# LNB.net
KiCad netlist of a schematic drawn in EAGLE
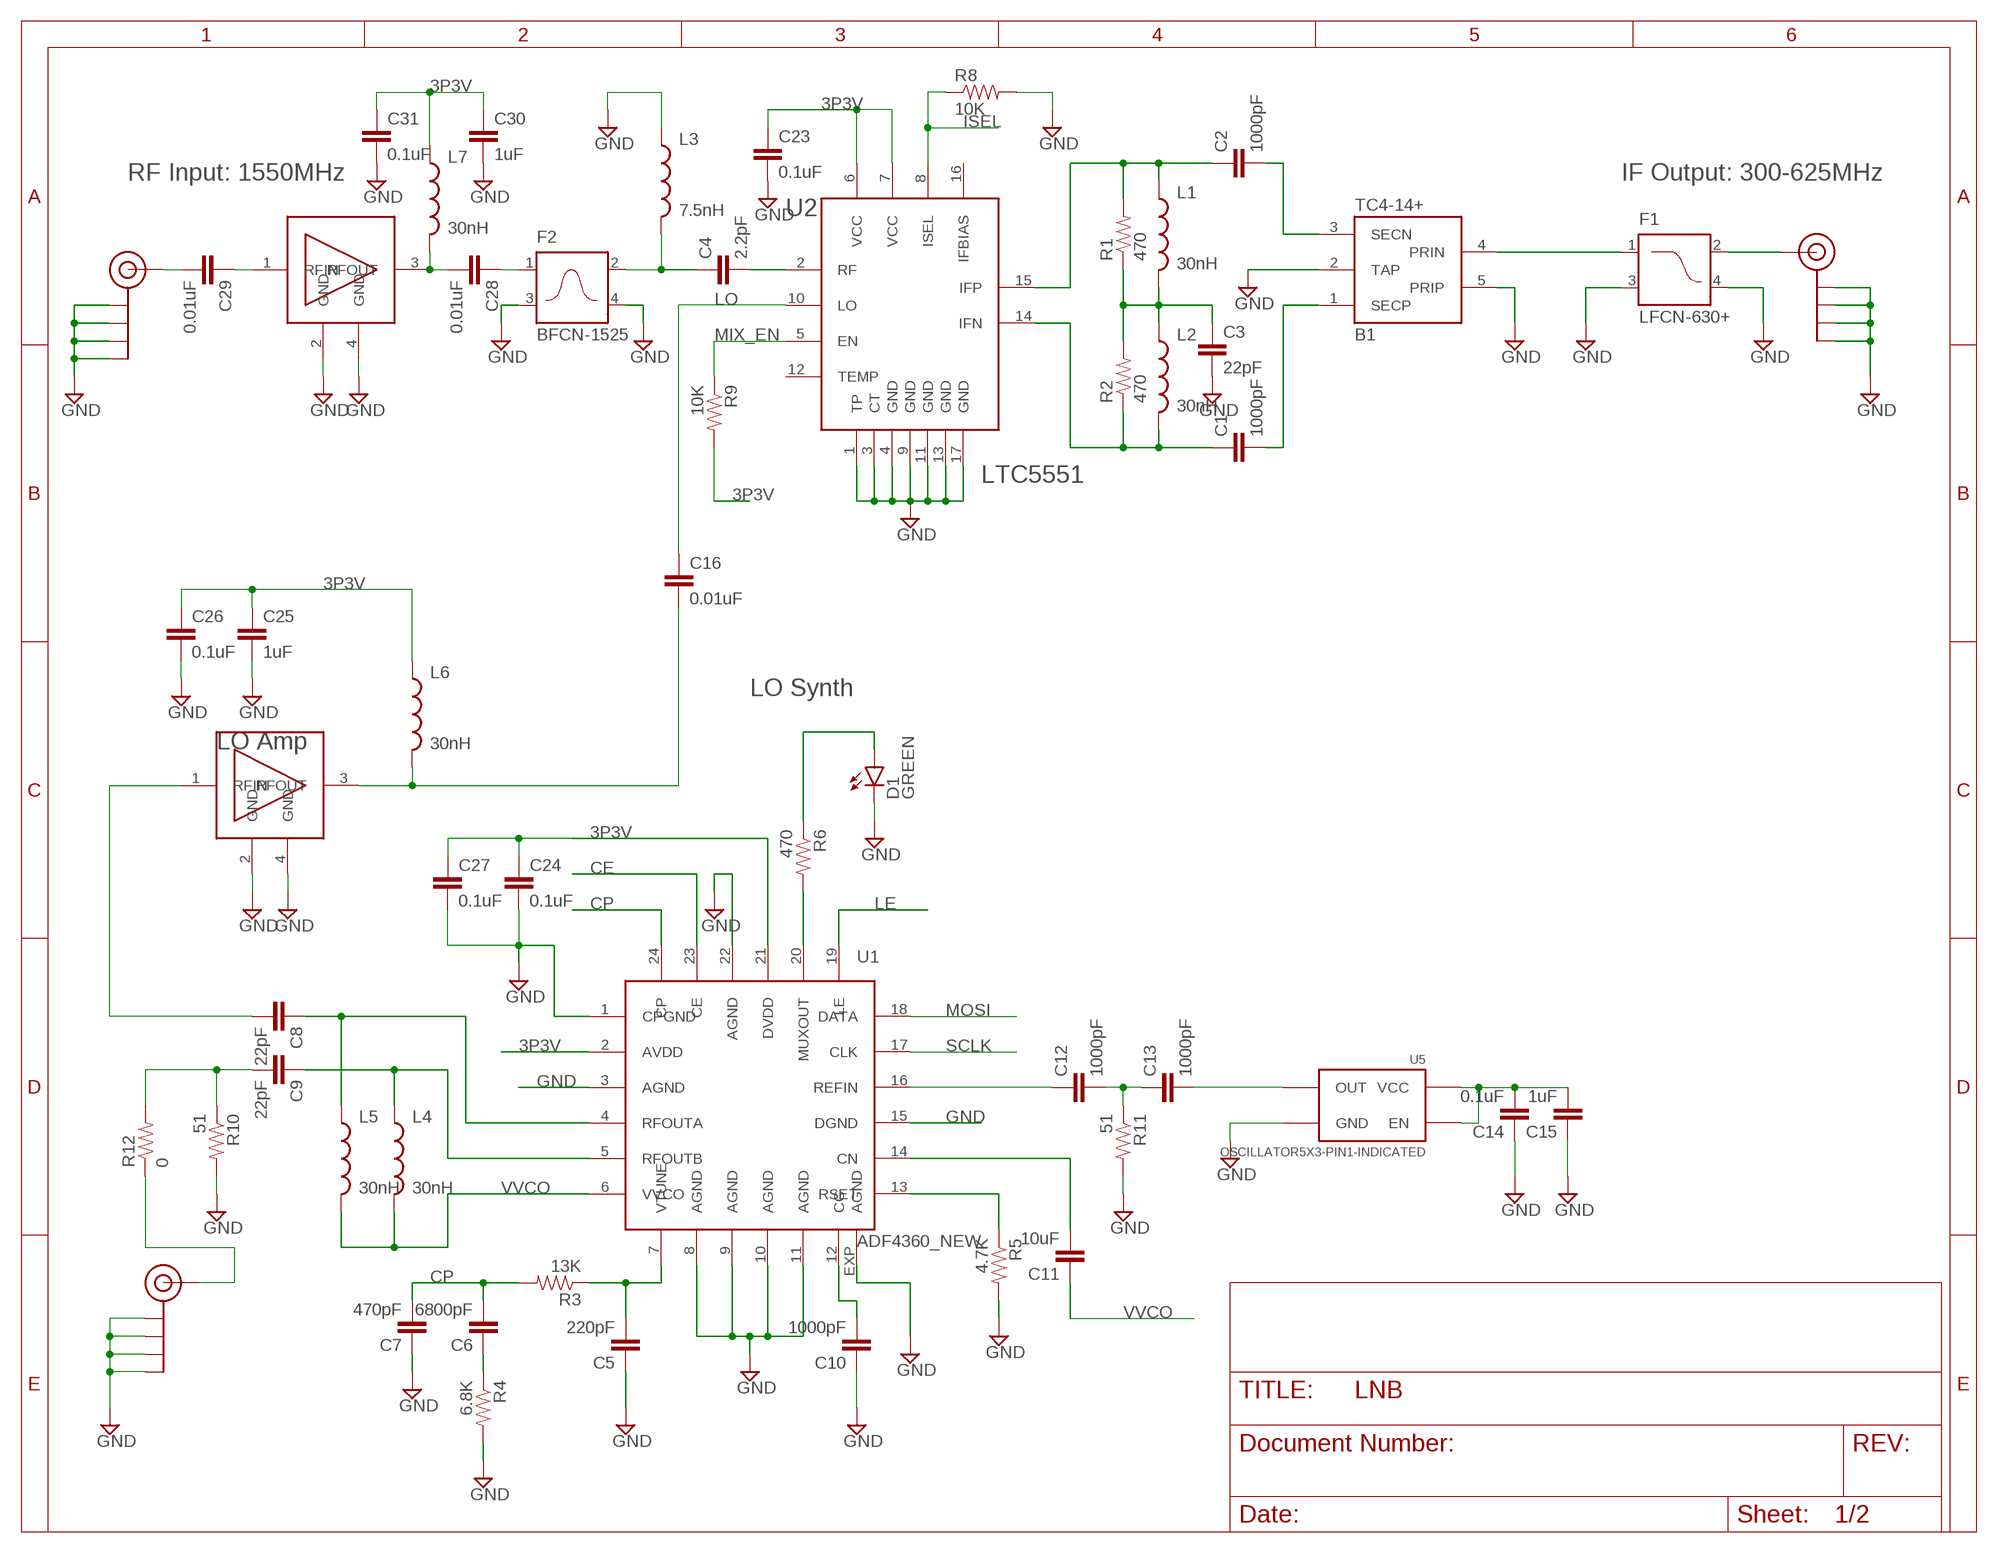
[diagram p0: schematic, sheet 1]
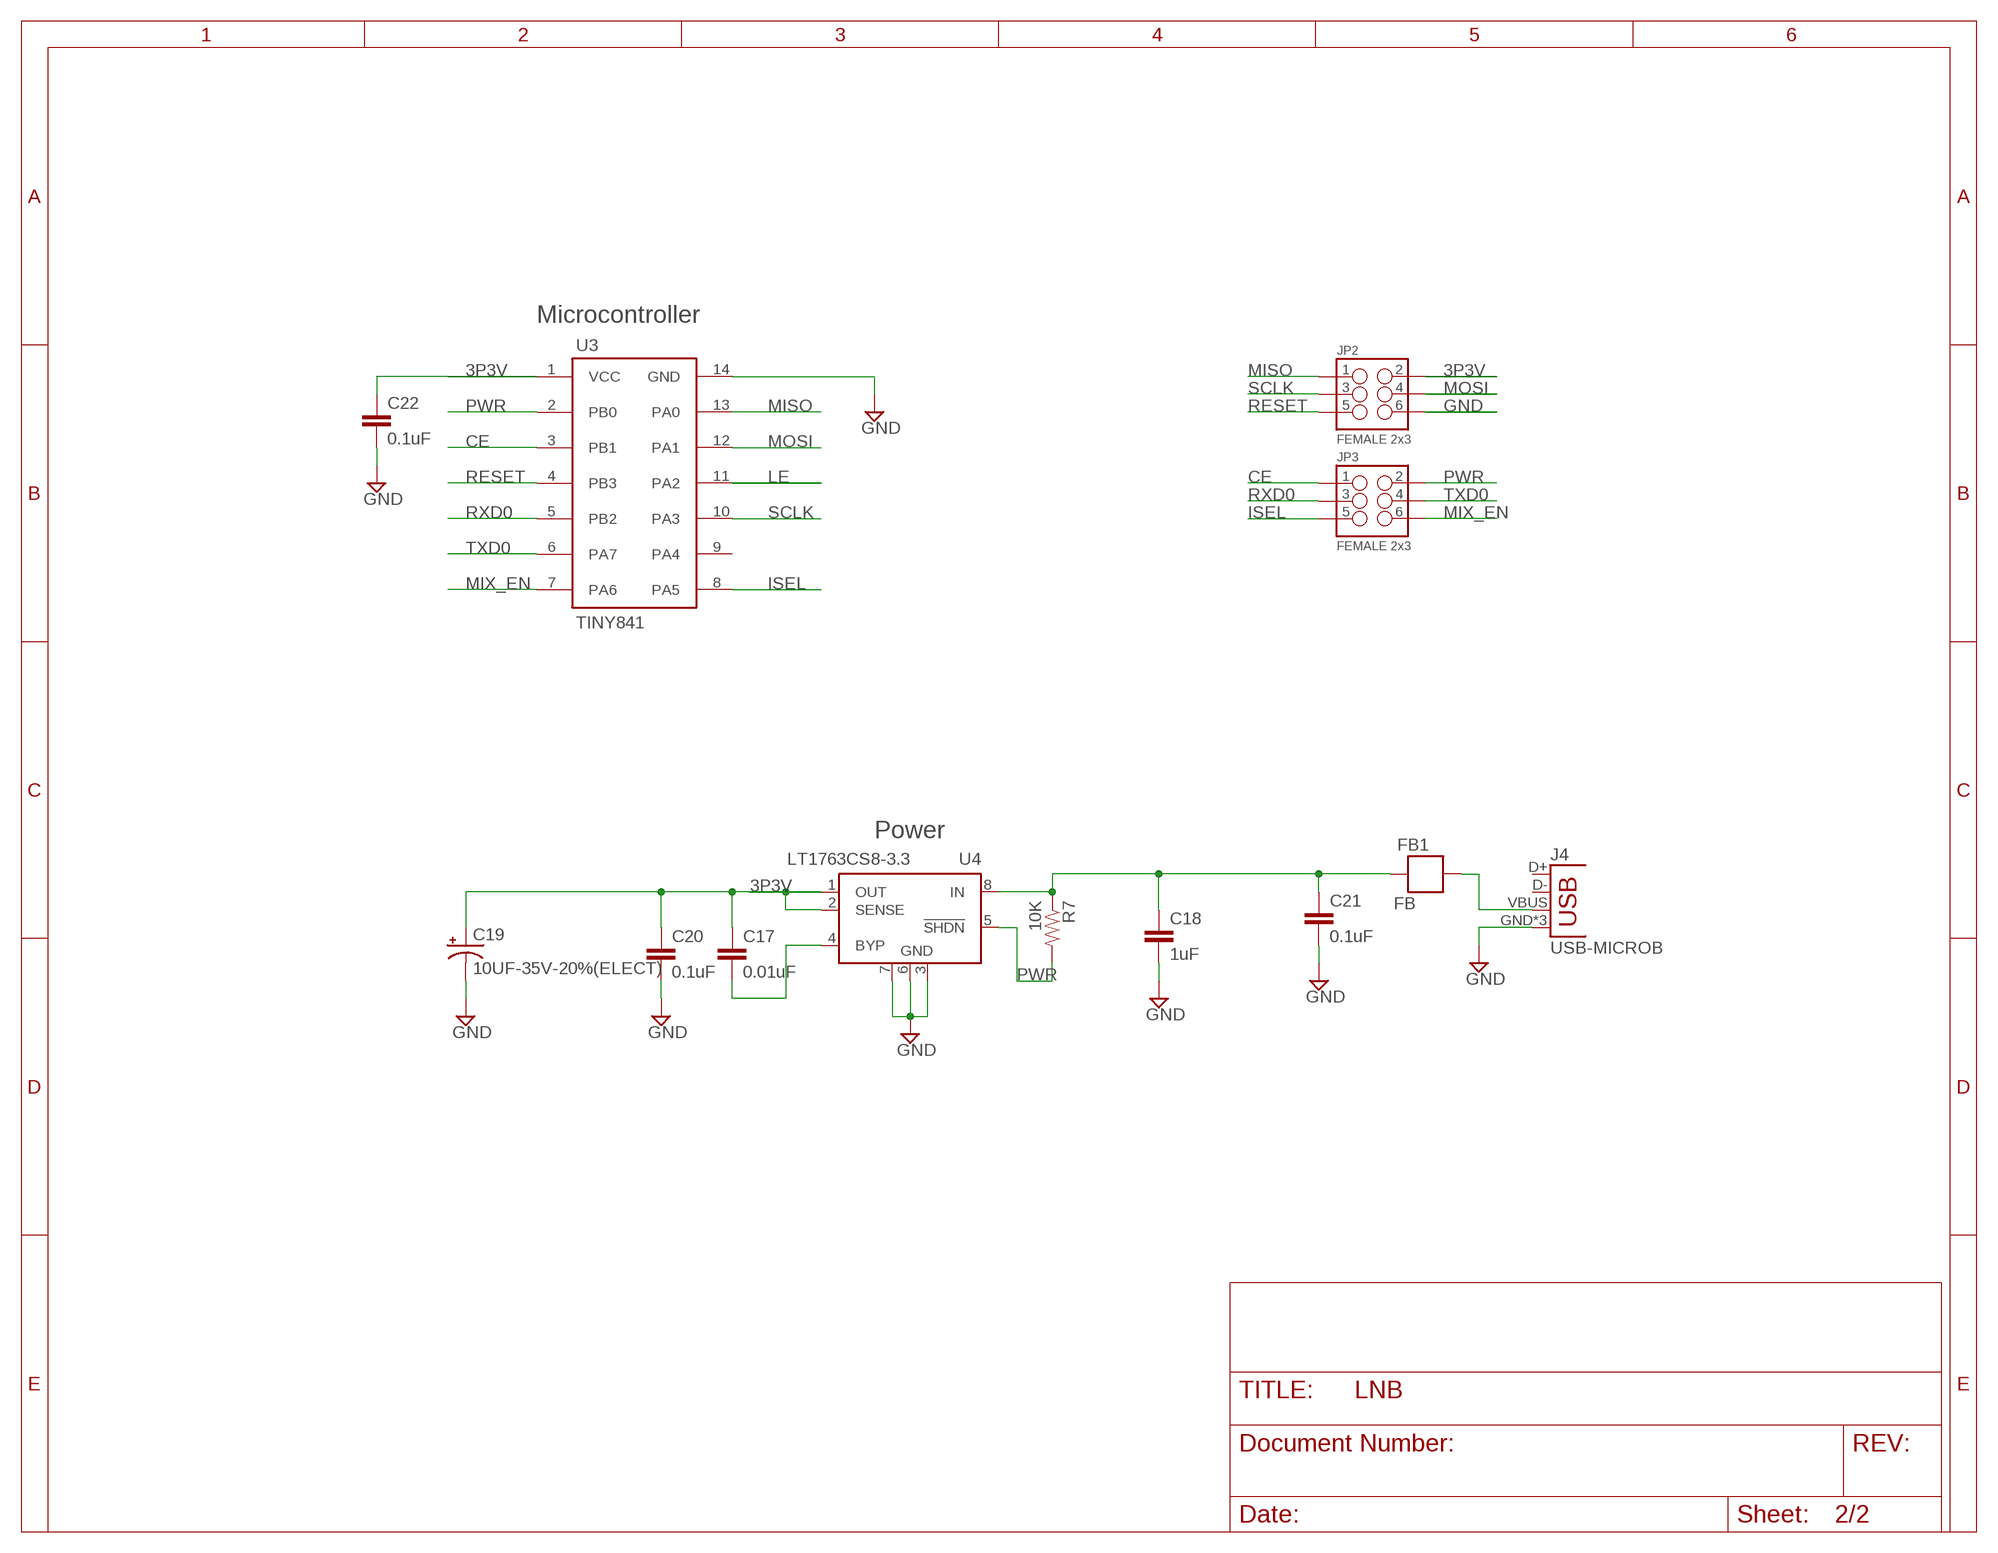
[diagram p1: schematic, sheet 2]

(export (version "E")
  (design (tool "Eeschema 10.0.6"))
  (components
    (comp (ref "B1")
      (value "TC4-14+")
      (footprint "eagle-import:AT224-1")
      (libsource (lib "eagle-import") (part "TC4-14+"))
    )
    (comp (ref "C1")
      (value "1000pF")
      (footprint "eagle-import:0603-CAP")
      (libsource (lib "eagle-import") (part "CAP0603-CAP"))
    )
    (comp (ref "C2")
      (value "1000pF")
      (footprint "eagle-import:0603-CAP")
      (libsource (lib "eagle-import") (part "CAP0603-CAP"))
    )
    (comp (ref "C3")
      (value "22pF")
      (footprint "eagle-import:0603-CAP")
      (libsource (lib "eagle-import") (part "CAP0603-CAP"))
    )
    (comp (ref "C4")
      (value "2.2pF")
      (footprint "eagle-import:0603-CAP")
      (libsource (lib "eagle-import") (part "CAP0603-CAP"))
    )
    (comp (ref "C5")
      (value "220pF")
      (footprint "eagle-import:0603-CAP")
      (libsource (lib "eagle-import") (part "CAP0603-CAP"))
    )
    (comp (ref "C6")
      (value "6800pF")
      (footprint "eagle-import:0603-CAP")
      (libsource (lib "eagle-import") (part "CAP0603-CAP"))
    )
    (comp (ref "C7")
      (value "470pF")
      (footprint "eagle-import:0603-CAP")
      (libsource (lib "eagle-import") (part "CAP0603-CAP"))
    )
    (comp (ref "C8")
      (value "22pF")
      (footprint "eagle-import:0603-CAP")
      (libsource (lib "eagle-import") (part "CAP0603-CAP"))
    )
    (comp (ref "C9")
      (value "22pF")
      (footprint "eagle-import:0603-CAP")
      (libsource (lib "eagle-import") (part "CAP0603-CAP"))
    )
    (comp (ref "C10")
      (value "1000pF")
      (footprint "eagle-import:0603-CAP")
      (libsource (lib "eagle-import") (part "CAP0603-CAP"))
    )
    (comp (ref "C11")
      (value "10uF")
      (footprint "eagle-import:0603-CAP")
      (libsource (lib "eagle-import") (part "CAP0603-CAP"))
    )
    (comp (ref "C12")
      (value "1000pF")
      (footprint "eagle-import:0603-CAP")
      (libsource (lib "eagle-import") (part "CAP0603-CAP"))
    )
    (comp (ref "C13")
      (value "1000pF")
      (footprint "eagle-import:0603-CAP")
      (libsource (lib "eagle-import") (part "CAP0603-CAP"))
    )
    (comp (ref "C14")
      (value "0.1uF")
      (footprint "eagle-import:0603-CAP")
      (libsource (lib "eagle-import") (part "CAP0603-CAP"))
    )
    (comp (ref "C15")
      (value "1uF")
      (footprint "eagle-import:0603-CAP")
      (libsource (lib "eagle-import") (part "CAP0603-CAP"))
    )
    (comp (ref "C16")
      (value "0.01uF")
      (footprint "eagle-import:0603-CAP")
      (libsource (lib "eagle-import") (part "CAP0603-CAP"))
    )
    (comp (ref "C23")
      (value "0.1uF")
      (footprint "eagle-import:0603-CAP")
      (libsource (lib "eagle-import") (part "CAP0603-CAP"))
    )
    (comp (ref "C24")
      (value "0.1uF")
      (footprint "eagle-import:0603-CAP")
      (libsource (lib "eagle-import") (part "CAP0603-CAP"))
    )
    (comp (ref "C25")
      (value "1uF")
      (footprint "eagle-import:1206")
      (libsource (lib "eagle-import") (part "CAP1206"))
    )
    (comp (ref "C26")
      (value "0.1uF")
      (footprint "eagle-import:0603-CAP")
      (libsource (lib "eagle-import") (part "CAP0603-CAP"))
    )
    (comp (ref "C27")
      (value "0.1uF")
      (footprint "eagle-import:0603-CAP")
      (libsource (lib "eagle-import") (part "CAP0603-CAP"))
    )
    (comp (ref "C28")
      (value "0.01uF")
      (footprint "eagle-import:0603-CAP")
      (libsource (lib "eagle-import") (part "CAP0603-CAP"))
    )
    (comp (ref "C29")
      (value "0.01uF")
      (footprint "eagle-import:0603-CAP")
      (libsource (lib "eagle-import") (part "CAP0603-CAP"))
    )
    (comp (ref "C30")
      (value "1uF")
      (footprint "eagle-import:1206")
      (libsource (lib "eagle-import") (part "CAP1206"))
    )
    (comp (ref "C31")
      (value "0.1uF")
      (footprint "eagle-import:0603-CAP")
      (libsource (lib "eagle-import") (part "CAP0603-CAP"))
    )
    (comp (ref "D1")
      (value "GREEN")
      (footprint "eagle-import:LED-0603")
      (libsource (lib "eagle-import") (part "LED-GREEN0603"))
    )
    (comp (ref "F1")
      (value "LFCN-630+")
      (footprint "eagle-import:FV1206_MC")
      (libsource (lib "eagle-import") (part "LFCN-630+"))
    )
    (comp (ref "F2")
      (value "BFCN-1525")
      (footprint "eagle-import:FV1206_MC")
      (libsource (lib "eagle-import") (part "BFCN-1525"))
    )
    (comp (ref "J$1")
      (value "SMA_EDGE")
      (footprint "eagle-import:SMA-EDGE")
      (libsource (lib "eagle-import") (part "SMA_EDGE"))
    )
    (comp (ref "J2")
      (value "SMA_EDGE")
      (footprint "eagle-import:SMA-EDGE")
      (libsource (lib "eagle-import") (part "SMA_EDGE"))
    )
    (comp (ref "J3")
      (value "SMA_EDGE")
      (footprint "eagle-import:SMA-EDGE")
      (libsource (lib "eagle-import") (part "SMA_EDGE"))
    )
    (comp (ref "L1")
      (value "30nH")
      (footprint "eagle-import:0603")
      (libsource (lib "eagle-import") (part "INDUCTOR30OHM,1.8A"))
    )
    (comp (ref "L2")
      (value "30nH")
      (footprint "eagle-import:0603")
      (libsource (lib "eagle-import") (part "INDUCTOR30OHM,1.8A"))
    )
    (comp (ref "L3")
      (value "7.5nH")
      (footprint "eagle-import:0603")
      (libsource (lib "eagle-import") (part "INDUCTOR30OHM,1.8A"))
    )
    (comp (ref "L4")
      (value "30nH")
      (footprint "eagle-import:0603")
      (libsource (lib "eagle-import") (part "INDUCTOR30OHM,1.8A"))
    )
    (comp (ref "L5")
      (value "30nH")
      (footprint "eagle-import:0603")
      (libsource (lib "eagle-import") (part "INDUCTOR30OHM,1.8A"))
    )
    (comp (ref "L6")
      (value "30nH")
      (footprint "eagle-import:0603")
      (libsource (lib "eagle-import") (part "INDUCTOR30OHM,1.8A"))
    )
    (comp (ref "L7")
      (value "30nH")
      (footprint "eagle-import:0603")
      (libsource (lib "eagle-import") (part "INDUCTOR30OHM,1.8A"))
    )
    (comp (ref "R1")
      (value "470")
      (footprint "eagle-import:0603-RES")
      (libsource (lib "eagle-import") (part "RESISTOR0603-RES"))
    )
    (comp (ref "R2")
      (value "470")
      (footprint "eagle-import:0603-RES")
      (libsource (lib "eagle-import") (part "RESISTOR0603-RES"))
    )
    (comp (ref "R3")
      (value "13K")
      (footprint "eagle-import:0603-RES")
      (libsource (lib "eagle-import") (part "RESISTOR0603-RES"))
    )
    (comp (ref "R4")
      (value "6.8K")
      (footprint "eagle-import:0603-RES")
      (libsource (lib "eagle-import") (part "RESISTOR0603-RES"))
    )
    (comp (ref "R5")
      (value "4.7K")
      (footprint "eagle-import:0603-RES")
      (libsource (lib "eagle-import") (part "RESISTOR0603-RES"))
    )
    (comp (ref "R6")
      (value "470")
      (footprint "eagle-import:0603-RES")
      (libsource (lib "eagle-import") (part "RESISTOR0603-RES"))
    )
    (comp (ref "R8")
      (value "10K")
      (footprint "eagle-import:0603-RES")
      (libsource (lib "eagle-import") (part "RESISTOR0603-RES"))
    )
    (comp (ref "R9")
      (value "10K")
      (footprint "eagle-import:0603-RES")
      (libsource (lib "eagle-import") (part "RESISTOR0603-RES"))
    )
    (comp (ref "R10")
      (value "51")
      (footprint "eagle-import:0603-RES")
      (libsource (lib "eagle-import") (part "RESISTOR0603-RES"))
    )
    (comp (ref "R11")
      (value "51")
      (footprint "eagle-import:0603-RES")
      (libsource (lib "eagle-import") (part "RESISTOR0603-RES"))
    )
    (comp (ref "R12")
      (value "0")
      (footprint "eagle-import:0603-RES")
      (libsource (lib "eagle-import") (part "RESISTOR0603-RES"))
    )
    (comp (ref "U1")
      (value "ADF4360_NEW")
      (footprint "eagle-import:LFCSP24")
      (libsource (lib "eagle-import") (part "ADF4360_NEW"))
    )
    (comp (ref "U2")
      (value "LTC5551")
      (footprint "eagle-import:QFN16-4X4")
      (libsource (lib "eagle-import") (part "LTC5551"))
    )
    (comp (ref "U5")
      (value "OSCILLATOR5X3-PIN1-INDICATED")
      (footprint "eagle-import:CRYSTAL-OSC-SMD-5X3")
      (libsource (lib "eagle-import") (part "OSCILLATOR5X3-PIN1-INDICATED"))
    )
    (comp (ref "U6")
      (value "PGA-105+")
      (footprint "eagle-import:SOT-89")
      (libsource (lib "eagle-import") (part "PGA-105+"))
    )
    (comp (ref "U7")
      (value "PGA-105+")
      (footprint "eagle-import:SOT-89")
      (libsource (lib "eagle-import") (part "PGA-105+"))
    )
    (comp (ref "C17")
      (value "0.01uF")
      (footprint "eagle-import:0603-CAP")
      (libsource (lib "eagle-import") (part "CAP0603-CAP"))
    )
    (comp (ref "C18")
      (value "1uF")
      (footprint "eagle-import:1206")
      (libsource (lib "eagle-import") (part "CAP1206"))
    )
    (comp (ref "C19")
      (value "10UF-35V-20%(ELECT)")
      (footprint "eagle-import:PANASONIC_C")
      (libsource (lib "eagle-import") (part "10UF-35V-20%(ELECT)"))
    )
    (comp (ref "C20")
      (value "0.1uF")
      (footprint "eagle-import:0603-CAP")
      (libsource (lib "eagle-import") (part "CAP0603-CAP"))
    )
    (comp (ref "C21")
      (value "0.1uF")
      (footprint "eagle-import:0603-CAP")
      (libsource (lib "eagle-import") (part "CAP0603-CAP"))
    )
    (comp (ref "C22")
      (value "0.1uF")
      (footprint "eagle-import:0603-CAP")
      (libsource (lib "eagle-import") (part "CAP0603-CAP"))
    )
    (comp (ref "FB1")
      (value "FB")
      (footprint "eagle-import:0603")
      (libsource (lib "eagle-import") (part "FB"))
    )
    (comp (ref "J4")
      (value "USB-MICROB")
      (footprint "eagle-import:USB-MICROB")
      (libsource (lib "eagle-import") (part "USB-MICROB"))
    )
    (comp (ref "JP2")
      (value "FEMALE 2x3")
      (footprint "eagle-import:2X3")
      (libsource (lib "eagle-import") (part "M03X2FEMALE"))
    )
    (comp (ref "JP3")
      (value "FEMALE 2x3")
      (footprint "eagle-import:2X3")
      (libsource (lib "eagle-import") (part "M03X2FEMALE"))
    )
    (comp (ref "R7")
      (value "10K")
      (footprint "eagle-import:0603-RES")
      (libsource (lib "eagle-import") (part "RESISTOR0603-RES"))
    )
    (comp (ref "U3")
      (value "TINY841")
      (footprint "eagle-import:SOIC14")
      (libsource (lib "eagle-import") (part "TINY841"))
    )
    (comp (ref "U4")
      (value "LT1763CS8-3.3")
      (footprint "eagle-import:SOIC8")
      (libsource (lib "eagle-import") (part "LT1763CS8-3.3"))
    )
  )
  (nets
    (net (code "1") (name "3P3V") (class "Default")
      (node (ref "C14") (pin "2") (pinfunction "2_2") (pintype "passive"))
      (node (ref "C15") (pin "2") (pinfunction "2_2") (pintype "passive"))
      (node (ref "C17") (pin "1") (pinfunction "1_1") (pintype "passive"))
      (node (ref "C19") (pin "+") (pinfunction "+_+") (pintype "passive"))
      (node (ref "C20") (pin "1") (pinfunction "1_1") (pintype "passive"))
      (node (ref "C22") (pin "1") (pinfunction "1_1") (pintype "passive"))
      (node (ref "C23") (pin "1") (pinfunction "1_1") (pintype "passive"))
      (node (ref "C24") (pin "1") (pinfunction "1_1") (pintype "passive"))
      (node (ref "C25") (pin "1") (pinfunction "1_1") (pintype "passive"))
      (node (ref "C26") (pin "1") (pinfunction "1_1") (pintype "passive"))
      (node (ref "C27") (pin "1") (pinfunction "1_1") (pintype "passive"))
      (node (ref "C30") (pin "1") (pinfunction "1_1") (pintype "passive"))
      (node (ref "C31") (pin "1") (pinfunction "1_1") (pintype "passive"))
      (node (ref "JP2") (pin "2") (pinfunction "2_2") (pintype "bidirectional"))
      (node (ref "L6") (pin "1") (pinfunction "1_1") (pintype "passive"))
      (node (ref "L7") (pin "1") (pinfunction "1_1") (pintype "passive"))
      (node (ref "R9") (pin "2") (pinfunction "2_2") (pintype "passive"))
      (node (ref "U1") (pin "2") (pinfunction "AVDD_2") (pintype "power_in"))
      (node (ref "U1") (pin "21") (pinfunction "DVDD_21") (pintype "power_in"))
      (node (ref "U2") (pin "6") (pinfunction "VCC_6") (pintype "bidirectional"))
      (node (ref "U2") (pin "7") (pinfunction "VCC_7") (pintype "bidirectional"))
      (node (ref "U3") (pin "1") (pinfunction "VCC_1") (pintype "bidirectional"))
      (node (ref "U4") (pin "1") (pinfunction "OUT_1") (pintype "passive"))
      (node (ref "U4") (pin "2") (pinfunction "SENSE_2") (pintype "input"))
      (node (ref "U5") (pin "1") (pinfunction "EN_1") (pintype "bidirectional"))
      (node (ref "U5") (pin "4") (pinfunction "VCC_4") (pintype "bidirectional"))
    )
    (net (code "2") (name "CE") (class "Default")
      (node (ref "JP3") (pin "1") (pinfunction "1_1") (pintype "bidirectional"))
      (node (ref "U1") (pin "23") (pinfunction "CE_23") (pintype "power_in"))
      (node (ref "U3") (pin "3") (pinfunction "PB1_3") (pintype "bidirectional"))
    )
    (net (code "3") (name "CP") (class "Default")
      (node (ref "C6") (pin "2") (pinfunction "2_2") (pintype "passive"))
      (node (ref "C7") (pin "2") (pinfunction "2_2") (pintype "passive"))
      (node (ref "R3") (pin "2") (pinfunction "2_2") (pintype "passive"))
      (node (ref "U1") (pin "24") (pinfunction "CP_24") (pintype "power_in"))
    )
    (net (code "4") (name "GND") (class "Default")
      (node (ref "B1") (pin "2") (pinfunction "TAP_2") (pintype "bidirectional"))
      (node (ref "B1") (pin "5") (pinfunction "PRIP_5") (pintype "bidirectional"))
      (node (ref "C10") (pin "1") (pinfunction "1_1") (pintype "passive"))
      (node (ref "C14") (pin "1") (pinfunction "1_1") (pintype "passive"))
      (node (ref "C15") (pin "1") (pinfunction "1_1") (pintype "passive"))
      (node (ref "C18") (pin "2") (pinfunction "2_2") (pintype "passive"))
      (node (ref "C19") (pin "-") (pinfunction "-_-") (pintype "passive"))
      (node (ref "C20") (pin "2") (pinfunction "2_2") (pintype "passive"))
      (node (ref "C21") (pin "2") (pinfunction "2_2") (pintype "passive"))
      (node (ref "C22") (pin "2") (pinfunction "2_2") (pintype "passive"))
      (node (ref "C23") (pin "2") (pinfunction "2_2") (pintype "passive"))
      (node (ref "C24") (pin "2") (pinfunction "2_2") (pintype "passive"))
      (node (ref "C25") (pin "2") (pinfunction "2_2") (pintype "passive"))
      (node (ref "C26") (pin "2") (pinfunction "2_2") (pintype "passive"))
      (node (ref "C27") (pin "2") (pinfunction "2_2") (pintype "passive"))
      (node (ref "C3") (pin "2") (pinfunction "2_2") (pintype "passive"))
      (node (ref "C30") (pin "2") (pinfunction "2_2") (pintype "passive"))
      (node (ref "C31") (pin "2") (pinfunction "2_2") (pintype "passive"))
      (node (ref "C5") (pin "1") (pinfunction "1_1") (pintype "passive"))
      (node (ref "C7") (pin "1") (pinfunction "1_1") (pintype "passive"))
      (node (ref "D1") (pin "C") (pinfunction "C_C") (pintype "passive"))
      (node (ref "F1") (pin "3") (pinfunction "GND_3") (pintype "input"))
      (node (ref "F1") (pin "4") (pinfunction "GND_4") (pintype "input"))
      (node (ref "F2") (pin "3") (pinfunction "GND_3") (pintype "input"))
      (node (ref "F2") (pin "4") (pinfunction "GND_4") (pintype "input"))
      (node (ref "J$1") (pin "GND@0") (pinfunction "GND_GND@0") (pintype "bidirectional"))
      (node (ref "J$1") (pin "GND@1") (pinfunction "GND_GND@1") (pintype "bidirectional"))
      (node (ref "J$1") (pin "GND@2") (pinfunction "GND_GND@2") (pintype "bidirectional"))
      (node (ref "J$1") (pin "GND@3") (pinfunction "GND_GND@3") (pintype "bidirectional"))
      (node (ref "J2") (pin "GND@0") (pinfunction "GND_GND@0") (pintype "bidirectional"))
      (node (ref "J2") (pin "GND@1") (pinfunction "GND_GND@1") (pintype "bidirectional"))
      (node (ref "J2") (pin "GND@2") (pinfunction "GND_GND@2") (pintype "bidirectional"))
      (node (ref "J2") (pin "GND@3") (pinfunction "GND_GND@3") (pintype "bidirectional"))
      (node (ref "J3") (pin "GND@0") (pinfunction "GND_GND@0") (pintype "bidirectional"))
      (node (ref "J3") (pin "GND@1") (pinfunction "GND_GND@1") (pintype "bidirectional"))
      (node (ref "J3") (pin "GND@2") (pinfunction "GND_GND@2") (pintype "bidirectional"))
      (node (ref "J3") (pin "GND@3") (pinfunction "GND_GND@3") (pintype "bidirectional"))
      (node (ref "J4") (pin "GND") (pinfunction "GND_GND") (pintype "bidirectional"))
      (node (ref "J4") (pin "MT1") (pinfunction "GND_MT1") (pintype "bidirectional"))
      (node (ref "J4") (pin "MT2") (pinfunction "GND_MT2") (pintype "bidirectional"))
      (node (ref "JP2") (pin "6") (pinfunction "6_6") (pintype "bidirectional"))
      (node (ref "L3") (pin "1") (pinfunction "1_1") (pintype "passive"))
      (node (ref "R10") (pin "2") (pinfunction "2_2") (pintype "passive"))
      (node (ref "R11") (pin "2") (pinfunction "2_2") (pintype "passive"))
      (node (ref "R4") (pin "2") (pinfunction "2_2") (pintype "passive"))
      (node (ref "R5") (pin "2") (pinfunction "2_2") (pintype "passive"))
      (node (ref "R8") (pin "2") (pinfunction "2_2") (pintype "passive"))
      (node (ref "U1") (pin "1") (pinfunction "CPGND_1") (pintype "power_in"))
      (node (ref "U1") (pin "10") (pinfunction "AGND_10") (pintype "power_in"))
      (node (ref "U1") (pin "11") (pinfunction "AGND_11") (pintype "power_in"))
      (node (ref "U1") (pin "15") (pinfunction "DGND_15") (pintype "power_in"))
      (node (ref "U1") (pin "22") (pinfunction "AGND_22") (pintype "power_in"))
      (node (ref "U1") (pin "3") (pinfunction "AGND_3") (pintype "power_in"))
      (node (ref "U1") (pin "8") (pinfunction "AGND_8") (pintype "power_in"))
      (node (ref "U1") (pin "9") (pinfunction "AGND_9") (pintype "power_in"))
      (node (ref "U1") (pin "EXP") (pinfunction "AGND_EXP") (pintype "power_in"))
      (node (ref "U2") (pin "1") (pinfunction "TP_1") (pintype "bidirectional"))
      (node (ref "U2") (pin "11") (pinfunction "GND_11") (pintype "bidirectional"))
      (node (ref "U2") (pin "13") (pinfunction "GND_13") (pintype "bidirectional"))
      (node (ref "U2") (pin "17") (pinfunction "GND_17") (pintype "bidirectional"))
      (node (ref "U2") (pin "3") (pinfunction "CT_3") (pintype "bidirectional"))
      (node (ref "U2") (pin "4") (pinfunction "GND_4") (pintype "bidirectional"))
      (node (ref "U2") (pin "9") (pinfunction "GND_9") (pintype "bidirectional"))
      (node (ref "U3") (pin "14") (pinfunction "GND_14") (pintype "bidirectional"))
      (node (ref "U4") (pin "3") (pinfunction "GND_3") (pintype "power_in"))
      (node (ref "U4") (pin "6") (pinfunction "GND_6") (pintype "power_in"))
      (node (ref "U4") (pin "7") (pinfunction "GND_7") (pintype "power_in"))
      (node (ref "U5") (pin "2") (pinfunction "GND_2") (pintype "bidirectional"))
      (node (ref "U6") (pin "2") (pinfunction "GND_2") (pintype "bidirectional"))
      (node (ref "U6") (pin "4") (pinfunction "GND_4") (pintype "bidirectional"))
      (node (ref "U7") (pin "2") (pinfunction "GND_2") (pintype "bidirectional"))
      (node (ref "U7") (pin "4") (pinfunction "GND_4") (pintype "bidirectional"))
    )
    (net (code "5") (name "ISEL") (class "Default")
      (node (ref "JP3") (pin "5") (pinfunction "5_5") (pintype "bidirectional"))
      (node (ref "R8") (pin "1") (pinfunction "1_1") (pintype "passive"))
      (node (ref "U2") (pin "8") (pinfunction "ISEL_8") (pintype "bidirectional"))
      (node (ref "U3") (pin "8") (pinfunction "PA5_8") (pintype "bidirectional"))
    )
    (net (code "6") (name "LE") (class "Default")
      (node (ref "U1") (pin "19") (pinfunction "LE_19") (pintype "power_in"))
      (node (ref "U3") (pin "11") (pinfunction "PA2_11") (pintype "bidirectional"))
    )
    (net (code "7") (name "LO") (class "Default")
      (node (ref "C16") (pin "1") (pinfunction "1_1") (pintype "passive"))
      (node (ref "U2") (pin "10") (pinfunction "LO_10") (pintype "bidirectional"))
    )
    (net (code "8") (name "MISO") (class "Default")
      (node (ref "JP2") (pin "1") (pinfunction "1_1") (pintype "bidirectional"))
      (node (ref "U3") (pin "13") (pinfunction "PA0_13") (pintype "bidirectional"))
    )
    (net (code "9") (name "MIX_EN") (class "Default")
      (node (ref "JP3") (pin "6") (pinfunction "6_6") (pintype "bidirectional"))
      (node (ref "R9") (pin "1") (pinfunction "1_1") (pintype "passive"))
      (node (ref "U2") (pin "5") (pinfunction "EN_5") (pintype "bidirectional"))
      (node (ref "U3") (pin "7") (pinfunction "PA6_7") (pintype "bidirectional"))
    )
    (net (code "10") (name "MOSI") (class "Default")
      (node (ref "JP2") (pin "4") (pinfunction "4_4") (pintype "bidirectional"))
      (node (ref "U1") (pin "18") (pinfunction "DATA_18") (pintype "power_in"))
      (node (ref "U3") (pin "12") (pinfunction "PA1_12") (pintype "bidirectional"))
    )
    (net (code "11") (name "Net-(B1-PRIN)") (class "Default")
      (node (ref "B1") (pin "4") (pinfunction "PRIN_4") (pintype "bidirectional"))
      (node (ref "F1") (pin "1") (pinfunction "IN_1") (pintype "input"))
    )
    (net (code "12") (name "Net-(B1-SECN)") (class "Default")
      (node (ref "B1") (pin "3") (pinfunction "SECN_3") (pintype "bidirectional"))
      (node (ref "C2") (pin "2") (pinfunction "2_2") (pintype "passive"))
    )
    (net (code "13") (name "Net-(B1-SECP)") (class "Default")
      (node (ref "B1") (pin "1") (pinfunction "SECP_1") (pintype "bidirectional"))
      (node (ref "C1") (pin "2") (pinfunction "2_2") (pintype "passive"))
    )
    (net (code "14") (name "Net-(C3-Pad1)") (class "Default")
      (node (ref "C3") (pin "1") (pinfunction "1_1") (pintype "passive"))
      (node (ref "L1") (pin "2") (pinfunction "2_2") (pintype "passive"))
      (node (ref "L2") (pin "1") (pinfunction "1_1") (pintype "passive"))
      (node (ref "R1") (pin "1") (pinfunction "1_1") (pintype "passive"))
      (node (ref "R2") (pin "2") (pinfunction "2_2") (pintype "passive"))
    )
    (net (code "15") (name "Net-(C6-Pad1)") (class "Default")
      (node (ref "C6") (pin "1") (pinfunction "1_1") (pintype "passive"))
      (node (ref "R4") (pin "1") (pinfunction "1_1") (pintype "passive"))
    )
    (net (code "16") (name "Net-(C9-Pad2)") (class "Default")
      (node (ref "C9") (pin "2") (pinfunction "2_2") (pintype "passive"))
      (node (ref "R10") (pin "1") (pinfunction "1_1") (pintype "passive"))
      (node (ref "R12") (pin "2") (pinfunction "2_2") (pintype "passive"))
    )
    (net (code "17") (name "Net-(C12-Pad2)") (class "Default")
      (node (ref "C12") (pin "2") (pinfunction "2_2") (pintype "passive"))
      (node (ref "C13") (pin "1") (pinfunction "1_1") (pintype "passive"))
      (node (ref "R11") (pin "1") (pinfunction "1_1") (pintype "passive"))
    )
    (net (code "18") (name "Net-(D1-PadA)") (class "Default")
      (node (ref "D1") (pin "A") (pinfunction "A_A") (pintype "passive"))
      (node (ref "R6") (pin "1") (pinfunction "1_1") (pintype "passive"))
    )
    (net (code "19") (name "Net-(F1-OUT)") (class "Default")
      (node (ref "F1") (pin "2") (pinfunction "OUT_2") (pintype "input"))
      (node (ref "J$1") (pin "SIG") (pinfunction "SIGNAL_SIG") (pintype "bidirectional"))
    )
    (net (code "20") (name "Net-(F2-IN)") (class "Default")
      (node (ref "C28") (pin "1") (pinfunction "1_1") (pintype "passive"))
      (node (ref "F2") (pin "1") (pinfunction "IN_1") (pintype "input"))
    )
    (net (code "21") (name "Net-(F2-OUT)") (class "Default")
      (node (ref "C4") (pin "1") (pinfunction "1_1") (pintype "passive"))
      (node (ref "F2") (pin "2") (pinfunction "OUT_2") (pintype "input"))
      (node (ref "L3") (pin "2") (pinfunction "2_2") (pintype "passive"))
    )
    (net (code "22") (name "Net-(FB1-P$1)") (class "Default")
      (node (ref "FB1") (pin "1") (pinfunction "P$1_1") (pintype "bidirectional"))
      (node (ref "J4") (pin "VBUS") (pinfunction "VBUS_VBUS") (pintype "bidirectional"))
    )
    (net (code "23") (name "Net-(FB1-P$2)") (class "Default")
      (node (ref "C18") (pin "1") (pinfunction "1_1") (pintype "passive"))
      (node (ref "C21") (pin "1") (pinfunction "1_1") (pintype "passive"))
      (node (ref "FB1") (pin "2") (pinfunction "P$2_2") (pintype "bidirectional"))
      (node (ref "R7") (pin "1") (pinfunction "1_1") (pintype "passive"))
      (node (ref "U4") (pin "8") (pinfunction "IN_8") (pintype "input"))
    )
    (net (code "24") (name "Net-(J2-SIGNAL)") (class "Default")
      (node (ref "C29") (pin "2") (pinfunction "2_2") (pintype "passive"))
      (node (ref "J2") (pin "SIG") (pinfunction "SIGNAL_SIG") (pintype "bidirectional"))
    )
    (net (code "25") (name "Net-(J3-SIGNAL)") (class "Default")
      (node (ref "J3") (pin "SIG") (pinfunction "SIGNAL_SIG") (pintype "bidirectional"))
      (node (ref "R12") (pin "1") (pinfunction "1_1") (pintype "passive"))
    )
    (net (code "26") (name "Net-(U1-CC)") (class "Default")
      (node (ref "C10") (pin "2") (pinfunction "2_2") (pintype "passive"))
      (node (ref "U1") (pin "12") (pinfunction "CC_12") (pintype "power_in"))
    )
    (net (code "27") (name "Net-(U1-CN)") (class "Default")
      (node (ref "C11") (pin "2") (pinfunction "2_2") (pintype "passive"))
      (node (ref "U1") (pin "14") (pinfunction "CN_14") (pintype "power_in"))
    )
    (net (code "28") (name "Net-(U1-MUXOUT)") (class "Default")
      (node (ref "R6") (pin "2") (pinfunction "2_2") (pintype "passive"))
      (node (ref "U1") (pin "20") (pinfunction "MUXOUT_20") (pintype "power_in"))
    )
    (net (code "29") (name "Net-(U1-REFIN)") (class "Default")
      (node (ref "C12") (pin "1") (pinfunction "1_1") (pintype "passive"))
      (node (ref "U1") (pin "16") (pinfunction "REFIN_16") (pintype "power_in"))
    )
    (net (code "30") (name "Net-(U1-RFOUTA)") (class "Default")
      (node (ref "C8") (pin "1") (pinfunction "1_1") (pintype "passive"))
      (node (ref "L5") (pin "1") (pinfunction "1_1") (pintype "passive"))
      (node (ref "U1") (pin "4") (pinfunction "RFOUTA_4") (pintype "power_in"))
    )
    (net (code "31") (name "Net-(U1-RFOUTB)") (class "Default")
      (node (ref "C9") (pin "1") (pinfunction "1_1") (pintype "passive"))
      (node (ref "L4") (pin "1") (pinfunction "1_1") (pintype "passive"))
      (node (ref "U1") (pin "5") (pinfunction "RFOUTB_5") (pintype "power_in"))
    )
    (net (code "32") (name "Net-(U1-RSET)") (class "Default")
      (node (ref "R5") (pin "1") (pinfunction "1_1") (pintype "passive"))
      (node (ref "U1") (pin "13") (pinfunction "RSET_13") (pintype "power_in"))
    )
    (net (code "33") (name "Net-(U1-VTUNE)") (class "Default")
      (node (ref "C5") (pin "2") (pinfunction "2_2") (pintype "passive"))
      (node (ref "R3") (pin "1") (pinfunction "1_1") (pintype "passive"))
      (node (ref "U1") (pin "7") (pinfunction "VTUNE_7") (pintype "power_in"))
    )
    (net (code "34") (name "Net-(U2-IFN)") (class "Default")
      (node (ref "C1") (pin "1") (pinfunction "1_1") (pintype "passive"))
      (node (ref "L2") (pin "2") (pinfunction "2_2") (pintype "passive"))
      (node (ref "R2") (pin "1") (pinfunction "1_1") (pintype "passive"))
      (node (ref "U2") (pin "14") (pinfunction "IFN_14") (pintype "bidirectional"))
    )
    (net (code "35") (name "Net-(U2-IFP)") (class "Default")
      (node (ref "C2") (pin "1") (pinfunction "1_1") (pintype "passive"))
      (node (ref "L1") (pin "1") (pinfunction "1_1") (pintype "passive"))
      (node (ref "R1") (pin "2") (pinfunction "2_2") (pintype "passive"))
      (node (ref "U2") (pin "15") (pinfunction "IFP_15") (pintype "bidirectional"))
    )
    (net (code "36") (name "Net-(U2-RF)") (class "Default")
      (node (ref "C4") (pin "2") (pinfunction "2_2") (pintype "passive"))
      (node (ref "U2") (pin "2") (pinfunction "RF_2") (pintype "bidirectional"))
    )
    (net (code "37") (name "Net-(U4-BYP)") (class "Default")
      (node (ref "C17") (pin "2") (pinfunction "2_2") (pintype "passive"))
      (node (ref "U4") (pin "4") (pinfunction "BYP_4") (pintype "input"))
    )
    (net (code "38") (name "Net-(U5-OUT)") (class "Default")
      (node (ref "C13") (pin "2") (pinfunction "2_2") (pintype "passive"))
      (node (ref "U5") (pin "3") (pinfunction "OUT_3") (pintype "bidirectional"))
    )
    (net (code "39") (name "Net-(U6-RFIN)") (class "Default")
      (node (ref "C29") (pin "1") (pinfunction "1_1") (pintype "passive"))
      (node (ref "U6") (pin "1") (pinfunction "RFIN_1") (pintype "bidirectional"))
    )
    (net (code "40") (name "Net-(U6-RFOUT)") (class "Default")
      (node (ref "C28") (pin "2") (pinfunction "2_2") (pintype "passive"))
      (node (ref "L7") (pin "2") (pinfunction "2_2") (pintype "passive"))
      (node (ref "U6") (pin "3") (pinfunction "RFOUT_3") (pintype "bidirectional"))
    )
    (net (code "41") (name "Net-(U7-RFIN)") (class "Default")
      (node (ref "C8") (pin "2") (pinfunction "2_2") (pintype "passive"))
      (node (ref "U7") (pin "1") (pinfunction "RFIN_1") (pintype "bidirectional"))
    )
    (net (code "42") (name "Net-(U7-RFOUT)") (class "Default")
      (node (ref "C16") (pin "2") (pinfunction "2_2") (pintype "passive"))
      (node (ref "L6") (pin "2") (pinfunction "2_2") (pintype "passive"))
      (node (ref "U7") (pin "3") (pinfunction "RFOUT_3") (pintype "bidirectional"))
    )
    (net (code "43") (name "PWR") (class "Default")
      (node (ref "JP3") (pin "2") (pinfunction "2_2") (pintype "bidirectional"))
      (node (ref "R7") (pin "2") (pinfunction "2_2") (pintype "passive"))
      (node (ref "U3") (pin "2") (pinfunction "PB0_2") (pintype "bidirectional"))
      (node (ref "U4") (pin "5") (pinfunction "~{SHDN}_5") (pintype "input"))
    )
    (net (code "44") (name "RESET") (class "Default")
      (node (ref "JP2") (pin "5") (pinfunction "5_5") (pintype "bidirectional"))
      (node (ref "U3") (pin "4") (pinfunction "PB3_4") (pintype "bidirectional"))
    )
    (net (code "45") (name "RXD0") (class "Default")
      (node (ref "JP3") (pin "3") (pinfunction "3_3") (pintype "bidirectional"))
      (node (ref "U3") (pin "5") (pinfunction "PB2_5") (pintype "bidirectional"))
    )
    (net (code "46") (name "SCLK") (class "Default")
      (node (ref "JP2") (pin "3") (pinfunction "3_3") (pintype "bidirectional"))
      (node (ref "U1") (pin "17") (pinfunction "CLK_17") (pintype "power_in"))
      (node (ref "U3") (pin "10") (pinfunction "PA3_10") (pintype "bidirectional"))
    )
    (net (code "47") (name "TXD0") (class "Default")
      (node (ref "JP3") (pin "4") (pinfunction "4_4") (pintype "bidirectional"))
      (node (ref "U3") (pin "6") (pinfunction "PA7_6") (pintype "bidirectional"))
    )
    (net (code "48") (name "VVCO") (class "Default")
      (node (ref "C11") (pin "1") (pinfunction "1_1") (pintype "passive"))
      (node (ref "L4") (pin "2") (pinfunction "2_2") (pintype "passive"))
      (node (ref "L5") (pin "2") (pinfunction "2_2") (pintype "passive"))
      (node (ref "U1") (pin "6") (pinfunction "VVCO_6") (pintype "power_in"))
    )
    (net (code "49") (name "unconnected-(J4-PadD+)") (class "Default")
      (node (ref "J4") (pin "D+") (pinfunction "D+_D+") (pintype "bidirectional"))
    )
    (net (code "50") (name "unconnected-(J4-PadD-)") (class "Default")
      (node (ref "J4") (pin "D-") (pinfunction "D-_D-") (pintype "bidirectional"))
    )
    (net (code "51") (name "unconnected-(U2-IFBIAS-Pad16)") (class "Default")
      (node (ref "U2") (pin "16") (pinfunction "IFBIAS_16") (pintype "bidirectional"))
    )
    (net (code "52") (name "unconnected-(U2-TEMP-Pad12)") (class "Default")
      (node (ref "U2") (pin "12") (pinfunction "TEMP_12") (pintype "bidirectional"))
    )
    (net (code "53") (name "unconnected-(U3-PA4-Pad9)") (class "Default")
      (node (ref "U3") (pin "9") (pinfunction "PA4_9") (pintype "bidirectional"))
    )
  )
)
